# QCopterMV_IMU_Sch.net
KiCad netlist of a schematic drawn in Altium Designer
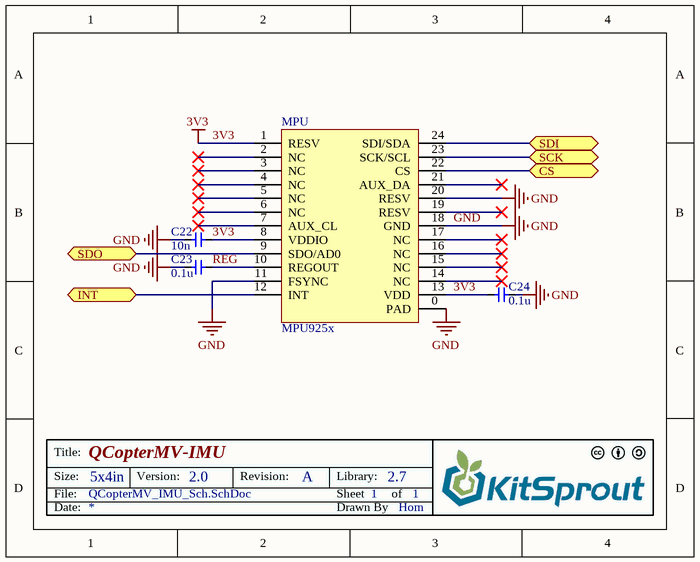
[diagram p0: QCopterMV_IMU_Sch.SchDoc]

(export (version "E")
  (design (tool "Eeschema 10.0.6"))
  (components
    (comp (ref "C22")
      (value "10n")
      (footprint "PCB_PassiveCap:CAP_0402")
      (description "Capacitor")
      (fields (field (name "Comment") "Cap_0402"))
      (libsource (lib "SCH_Passive") (part "Cap_0402"))
    )
    (comp (ref "C23")
      (value "0.1u")
      (footprint "PCB_PassiveCap:CAP_0402")
      (description "Capacitor")
      (fields (field (name "Comment") "Cap_0402"))
      (libsource (lib "SCH_Passive") (part "Cap_0402"))
    )
    (comp (ref "C24")
      (value "0.1u")
      (footprint "PCB_PassiveCap:CAP_0402")
      (description "Capacitor")
      (fields (field (name "Comment") "Cap_0402"))
      (libsource (lib "SCH_Passive") (part "Cap_0402"))
    )
    (comp (ref "MPU")
      (value "MPU925x")
      (footprint "PCB_IntegratedCircuit:QFN_P0.4_24")
      (description "Sensor Motion")
      (libsource (lib "SCH_IntegratedCircuit") (part "MPU925x"))
    )
  )
  (nets
    (net (code "1") (name "/CS") (class "Default")
      (node (ref "MPU") (pin "22") (pinfunction "CS_22") (pintype "passive"))
    )
    (net (code "2") (name "/INT") (class "Default")
      (node (ref "MPU") (pin "12") (pinfunction "INT_12") (pintype "passive"))
    )
    (net (code "3") (name "/REG") (class "Default")
      (node (ref "C23") (pin "2") (pinfunction "2_2") (pintype "passive"))
      (node (ref "MPU") (pin "10") (pinfunction "REGOUT_10") (pintype "passive"))
    )
    (net (code "4") (name "/SCK") (class "Default")
      (node (ref "MPU") (pin "23") (pinfunction "SCK/SCL_23") (pintype "passive"))
    )
    (net (code "5") (name "/SDI") (class "Default")
      (node (ref "MPU") (pin "24") (pinfunction "SDI/SDA_24") (pintype "passive"))
    )
    (net (code "6") (name "/SDO") (class "Default")
      (node (ref "MPU") (pin "9") (pinfunction "SDO/AD0_9") (pintype "passive"))
    )
    (net (code "7") (name "3V3") (class "Default")
      (node (ref "C22") (pin "2") (pinfunction "2_2") (pintype "passive"))
      (node (ref "C24") (pin "1") (pinfunction "1_1") (pintype "passive"))
      (node (ref "MPU") (pin "1") (pinfunction "RESV_1") (pintype "passive"))
      (node (ref "MPU") (pin "13") (pinfunction "VDD_13") (pintype "passive"))
      (node (ref "MPU") (pin "8") (pinfunction "VDDIO_8") (pintype "passive"))
    )
    (net (code "8") (name "GND") (class "Default")
      (node (ref "C22") (pin "1") (pinfunction "1_1") (pintype "passive"))
      (node (ref "C23") (pin "1") (pinfunction "1_1") (pintype "passive"))
      (node (ref "C24") (pin "2") (pinfunction "2_2") (pintype "passive"))
      (node (ref "MPU") (pin "0") (pinfunction "PAD_0") (pintype "passive"))
      (node (ref "MPU") (pin "11") (pinfunction "FSYNC_11") (pintype "passive"))
      (node (ref "MPU") (pin "18") (pinfunction "GND_18") (pintype "passive"))
      (node (ref "MPU") (pin "20") (pinfunction "RESV_20") (pintype "passive"))
    )
    (net (code "9") (name "unconnected-(MPU-AUX_CL-Pad7)") (class "Default")
      (node (ref "MPU") (pin "7") (pinfunction "AUX_CL_7") (pintype "passive+no_connect"))
    )
    (net (code "10") (name "unconnected-(MPU-AUX_DA-Pad21)") (class "Default")
      (node (ref "MPU") (pin "21") (pinfunction "AUX_DA_21") (pintype "passive+no_connect"))
    )
    (net (code "11") (name "unconnected-(MPU-NC-Pad2)") (class "Default")
      (node (ref "MPU") (pin "2") (pinfunction "NC_2") (pintype "passive+no_connect"))
    )
    (net (code "12") (name "unconnected-(MPU-NC-Pad3)") (class "Default")
      (node (ref "MPU") (pin "3") (pinfunction "NC_3") (pintype "passive+no_connect"))
    )
    (net (code "13") (name "unconnected-(MPU-NC-Pad4)") (class "Default")
      (node (ref "MPU") (pin "4") (pinfunction "NC_4") (pintype "passive+no_connect"))
    )
    (net (code "14") (name "unconnected-(MPU-NC-Pad5)") (class "Default")
      (node (ref "MPU") (pin "5") (pinfunction "NC_5") (pintype "passive+no_connect"))
    )
    (net (code "15") (name "unconnected-(MPU-NC-Pad6)") (class "Default")
      (node (ref "MPU") (pin "6") (pinfunction "NC_6") (pintype "passive+no_connect"))
    )
    (net (code "16") (name "unconnected-(MPU-NC-Pad14)") (class "Default")
      (node (ref "MPU") (pin "14") (pinfunction "NC_14") (pintype "passive+no_connect"))
    )
    (net (code "17") (name "unconnected-(MPU-NC-Pad15)") (class "Default")
      (node (ref "MPU") (pin "15") (pinfunction "NC_15") (pintype "passive+no_connect"))
    )
    (net (code "18") (name "unconnected-(MPU-NC-Pad16)") (class "Default")
      (node (ref "MPU") (pin "16") (pinfunction "NC_16") (pintype "passive+no_connect"))
    )
    (net (code "19") (name "unconnected-(MPU-NC-Pad17)") (class "Default")
      (node (ref "MPU") (pin "17") (pinfunction "NC_17") (pintype "passive+no_connect"))
    )
    (net (code "20") (name "unconnected-(MPU-RESV-Pad19)") (class "Default")
      (node (ref "MPU") (pin "19") (pinfunction "RESV_19") (pintype "passive+no_connect"))
    )
  )
)
